# NFC_Business_Card_No_SilkScreen_Just_Tra.net
KiCad netlist of a schematic drawn in EAGLE
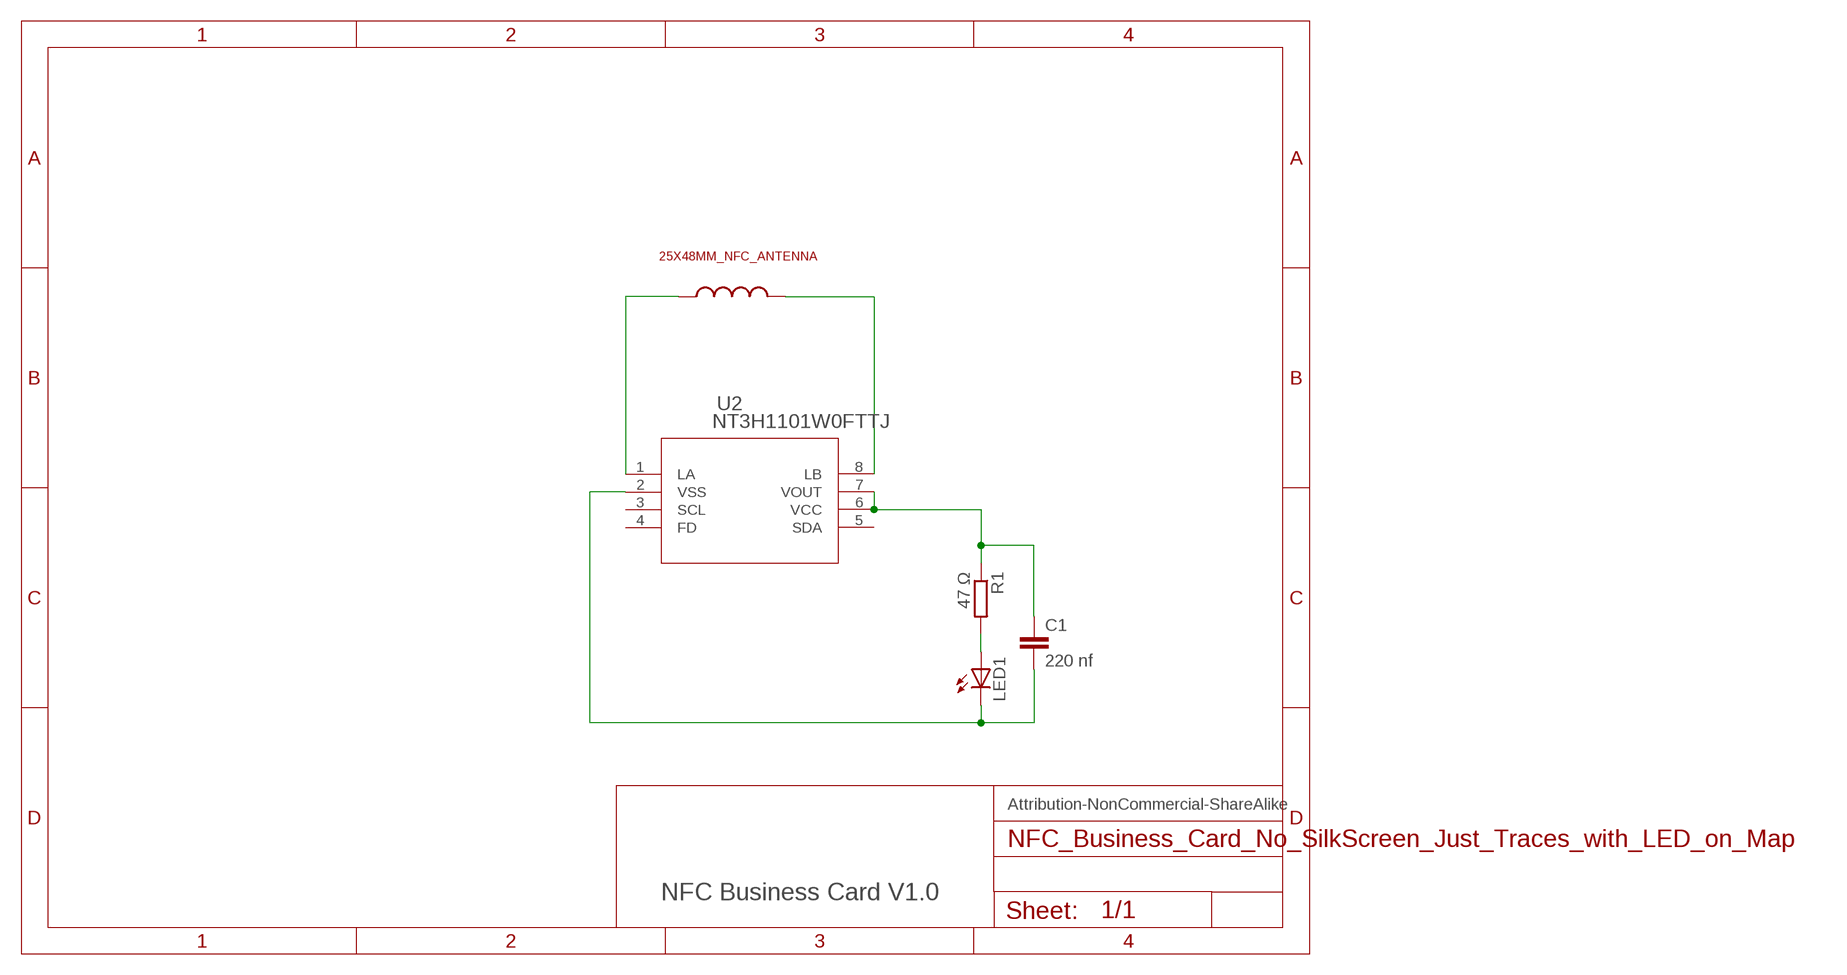
[diagram p0: schematic, sheet 1]

(export (version "E")
  (design (tool "Eeschema 10.0.6"))
  (components
    (comp (ref "ANT")
      (value "25X48MM_NFC_ANTENNA")
      (footprint "eagle-import:25X48MM_NFC")
      (libsource (lib "eagle-import") (part "25X48MM_NFC_ANTENNA"))
    )
    (comp (ref "C1")
      (value "220 nf")
      (footprint "eagle-import:C0603")
      (libsource (lib "eagle-import") (part "C-EUC0603"))
    )
    (comp (ref "LED1")
      (value "LEDSML0805")
      (footprint "eagle-import:SML0805")
      (libsource (lib "eagle-import") (part "LEDSML0805"))
    )
    (comp (ref "R1")
      (value "47 Ω")
      (footprint "eagle-import:R0603")
      (libsource (lib "eagle-import") (part "R-EU_R0603"))
    )
    (comp (ref "U2")
      (value "NT3H1101W0FTTJ")
      (footprint "eagle-import:TSSOP8_SOT505-1_NXP")
      (fields (field (name "COPYRIGHT") "Copyright (C) 2023 Ultra Librarian. All rights reserved."))
      (libsource (lib "eagle-import") (part "NT3H1101W0FTTJ"))
    )
  )
  (nets
    (net (code "1") (name "Net-(LED1-PadA)") (class "Default")
      (node (ref "LED1") (pin "A") (pinfunction "A_A") (pintype "passive"))
      (node (ref "R1") (pin "2") (pinfunction "2_2") (pintype "passive"))
    )
    (net (code "2") (name "Net-(U2-LA)") (class "Default")
      (node (ref "ANT") (pin "P$2") (pinfunction "P$2_P$2") (pintype "bidirectional"))
      (node (ref "U2") (pin "1") (pinfunction "LA_1") (pintype "passive"))
    )
    (net (code "3") (name "Net-(U2-LB)") (class "Default")
      (node (ref "ANT") (pin "P$1") (pinfunction "P$1_P$1") (pintype "bidirectional"))
      (node (ref "U2") (pin "8") (pinfunction "LB_8") (pintype "passive"))
    )
    (net (code "4") (name "Net-(U2-VCC)") (class "Default")
      (node (ref "C1") (pin "1") (pinfunction "1_1") (pintype "passive"))
      (node (ref "R1") (pin "1") (pinfunction "1_1") (pintype "passive"))
      (node (ref "U2") (pin "6") (pinfunction "VCC_6") (pintype "power_in"))
      (node (ref "U2") (pin "7") (pinfunction "VOUT_7") (pintype "power_in"))
    )
    (net (code "5") (name "Net-(U2-VSS)") (class "Default")
      (node (ref "C1") (pin "2") (pinfunction "2_2") (pintype "passive"))
      (node (ref "LED1") (pin "C") (pinfunction "C_C") (pintype "passive"))
      (node (ref "U2") (pin "2") (pinfunction "VSS_2") (pintype "passive"))
    )
    (net (code "6") (name "unconnected-(U2-FD-Pad4)") (class "Default")
      (node (ref "U2") (pin "4") (pinfunction "FD_4") (pintype "passive"))
    )
    (net (code "7") (name "unconnected-(U2-SCL-Pad3)") (class "Default")
      (node (ref "U2") (pin "3") (pinfunction "SCL_3") (pintype "passive"))
    )
    (net (code "8") (name "unconnected-(U2-SDA-Pad5)") (class "Default")
      (node (ref "U2") (pin "5") (pinfunction "SDA_5") (pintype "passive"))
    )
  )
)
